# SunbotSchematic_copy.net
KiCad netlist of a schematic drawn in EAGLE
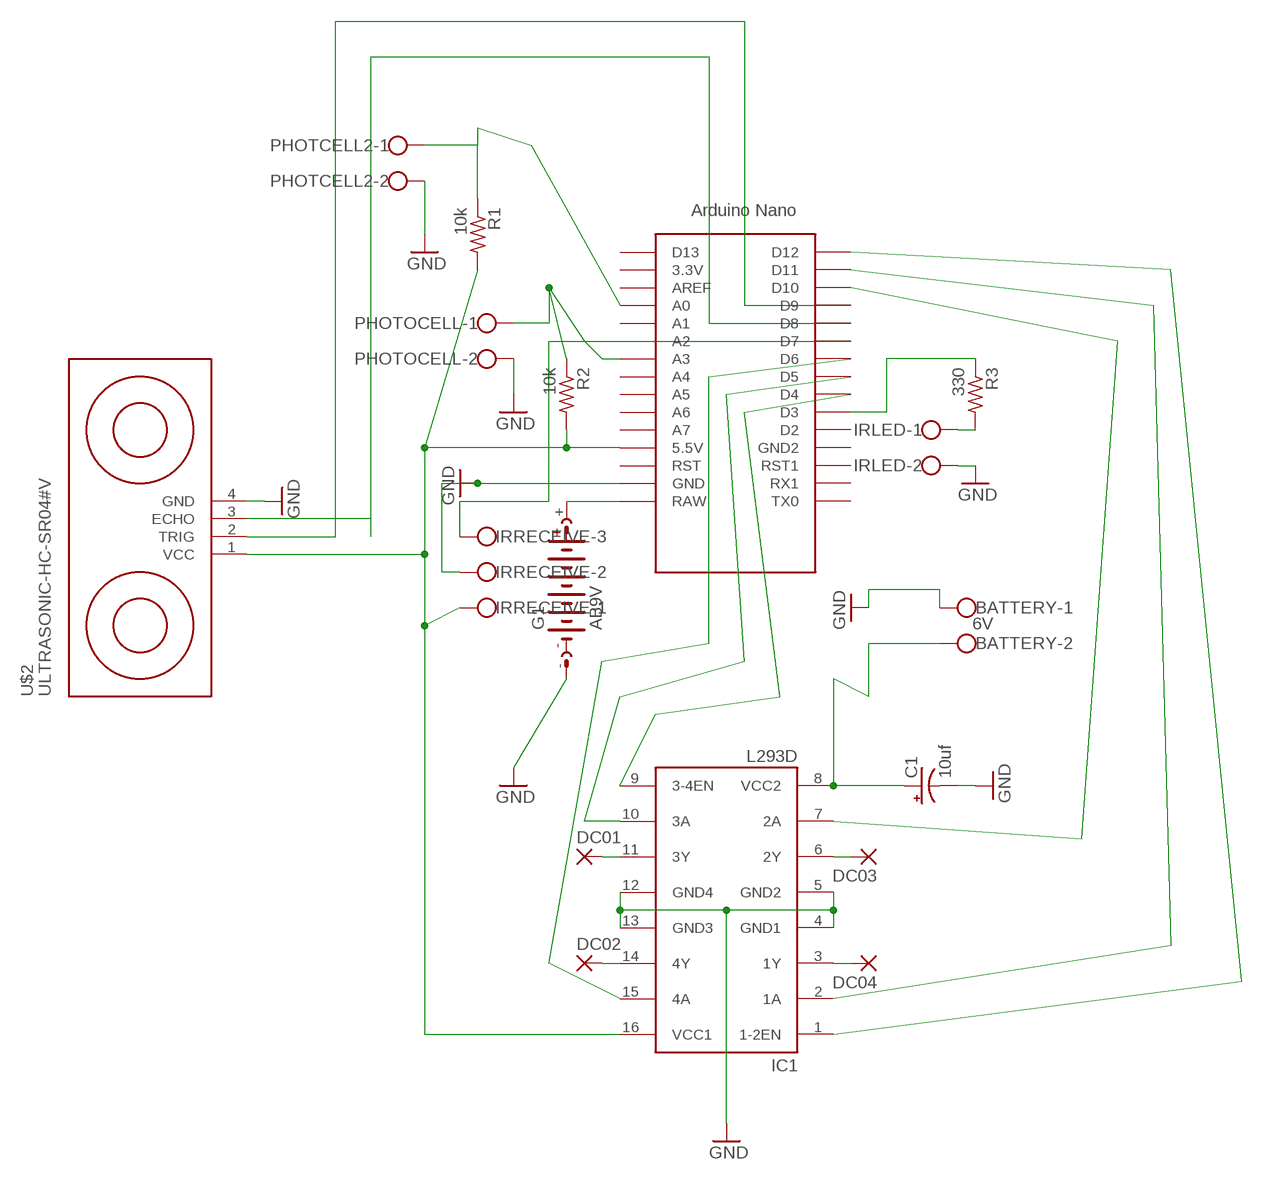
[diagram p0: schematic, sheet 1]

(export (version "E")
  (design (tool "Eeschema 10.0.6"))
  (components
    (comp (ref "BATTERY")
      (value "6V")
      (footprint "eagle-import:W237-102")
      (fields (field (name "MPN") "237-102"))
      (libsource (lib "eagle-import") (part "W237-102"))
    )
    (comp (ref "C1")
      (value "10uf")
      (footprint "eagle-import:E2-5")
      (libsource (lib "eagle-import") (part "CPOL-USE2-5"))
    )
    (comp (ref "DC01")
      (value "WIREPAD1,6/0,8")
      (footprint "eagle-import:1,6_0,8")
      (libsource (lib "eagle-import") (part "WIREPAD1,6/0,8"))
    )
    (comp (ref "DC02")
      (value "WIREPAD1,6/0,8")
      (footprint "eagle-import:1,6_0,8")
      (libsource (lib "eagle-import") (part "WIREPAD1,6/0,8"))
    )
    (comp (ref "DC03")
      (value "WIREPAD1,6/0,8")
      (footprint "eagle-import:1,6_0,8")
      (libsource (lib "eagle-import") (part "WIREPAD1,6/0,8"))
    )
    (comp (ref "DC04")
      (value "WIREPAD1,6/0,8")
      (footprint "eagle-import:1,6_0,8")
      (libsource (lib "eagle-import") (part "WIREPAD1,6/0,8"))
    )
    (comp (ref "G1")
      (value "AB9V")
      (footprint "eagle-import:AB9V")
      (libsource (lib "eagle-import") (part "AB9V"))
    )
    (comp (ref "IC1")
      (value "L293D")
      (footprint "eagle-import:DIL16")
      (libsource (lib "eagle-import") (part "L293D"))
    )
    (comp (ref "IRLED")
      (value "W237-102")
      (footprint "eagle-import:W237-102")
      (fields (field (name "MPN") "237-102"))
      (libsource (lib "eagle-import") (part "W237-102"))
    )
    (comp (ref "IRRECEIVE")
      (value "W237-103")
      (footprint "eagle-import:W237-103")
      (fields (field (name "MPN") "237-103"))
      (libsource (lib "eagle-import") (part "W237-103"))
    )
    (comp (ref "PHOTCELL2")
      (value "W237-102")
      (footprint "eagle-import:W237-102")
      (fields (field (name "MPN") "237-102"))
      (libsource (lib "eagle-import") (part "W237-102"))
    )
    (comp (ref "PHOTOCELL")
      (value "W237-102")
      (footprint "eagle-import:W237-102")
      (fields (field (name "MPN") "237-102"))
      (libsource (lib "eagle-import") (part "W237-102"))
    )
    (comp (ref "R1")
      (value "10k")
      (footprint "eagle-import:0204_7")
      (libsource (lib "eagle-import") (part "R-US_0204/7"))
    )
    (comp (ref "R2")
      (value "10k")
      (footprint "eagle-import:0204_7")
      (libsource (lib "eagle-import") (part "R-US_0204/7"))
    )
    (comp (ref "R3")
      (value "330")
      (footprint "eagle-import:0204_7")
      (libsource (lib "eagle-import") (part "R-US_0204/7"))
    )
    (comp (ref "U$1")
      (value "NANO")
      (footprint "eagle-import:NANO")
      (libsource (lib "eagle-import") (part "NANO"))
    )
    (comp (ref "U$2")
      (value "ULTRASONIC-HC-SR04#V")
      (footprint "eagle-import:ULTRASONIC-HC-SR04#V")
      (libsource (lib "eagle-import") (part "ULTRASONIC-HC-SR04#V"))
    )
  )
  (nets
    (net (code "1") (name "GND") (class "Default")
      (node (ref "BATTERY") (pin "1") (pinfunction "KL_1") (pintype "passive"))
      (node (ref "C1") (pin "-") (pinfunction "-_-") (pintype "passive"))
      (node (ref "G1") (pin "-") (pinfunction "-_-") (pintype "passive"))
      (node (ref "IC1") (pin "12") (pinfunction "GND4_12") (pintype "power_in"))
      (node (ref "IC1") (pin "13") (pinfunction "GND3_13") (pintype "power_in"))
      (node (ref "IC1") (pin "4") (pinfunction "GND1_4") (pintype "power_in"))
      (node (ref "IC1") (pin "5") (pinfunction "GND2_5") (pintype "power_in"))
      (node (ref "IRLED") (pin "2") (pinfunction "KL_2") (pintype "passive"))
      (node (ref "IRRECEIVE") (pin "2") (pinfunction "KL_2") (pintype "passive"))
      (node (ref "PHOTCELL2") (pin "2") (pinfunction "KL_2") (pintype "passive"))
      (node (ref "PHOTOCELL") (pin "2") (pinfunction "KL_2") (pintype "passive"))
      (node (ref "U$1") (pin "GND") (pinfunction "GND_GND") (pintype "bidirectional"))
      (node (ref "U$2") (pin "4") (pinfunction "GND_4") (pintype "power_in"))
    )
    (net (code "2") (name "Net-(BATTERYB-KL)") (class "Default")
      (node (ref "BATTERY") (pin "2") (pinfunction "KL_2") (pintype "passive"))
      (node (ref "C1") (pin "+") (pinfunction "+_+") (pintype "passive"))
      (node (ref "IC1") (pin "8") (pinfunction "VCC2_8") (pintype "power_in"))
    )
    (net (code "3") (name "Net-(DC01-P)") (class "Default")
      (node (ref "DC01") (pin "1") (pinfunction "P_1") (pintype "passive"))
      (node (ref "IC1") (pin "11") (pinfunction "3Y_11") (pintype "output"))
    )
    (net (code "4") (name "Net-(DC02-P)") (class "Default")
      (node (ref "DC02") (pin "1") (pinfunction "P_1") (pintype "passive"))
      (node (ref "IC1") (pin "14") (pinfunction "4Y_14") (pintype "output"))
    )
    (net (code "5") (name "Net-(DC03-P)") (class "Default")
      (node (ref "DC03") (pin "1") (pinfunction "P_1") (pintype "passive"))
      (node (ref "IC1") (pin "6") (pinfunction "2Y_6") (pintype "output"))
    )
    (net (code "6") (name "Net-(DC04-P)") (class "Default")
      (node (ref "DC04") (pin "1") (pinfunction "P_1") (pintype "passive"))
      (node (ref "IC1") (pin "3") (pinfunction "1Y_3") (pintype "output"))
    )
    (net (code "7") (name "Net-(G1-Pad+)") (class "Default")
      (node (ref "G1") (pin "+") (pinfunction "+_+") (pintype "passive"))
      (node (ref "U$1") (pin "RAW") (pinfunction "RAW_RAW") (pintype "bidirectional"))
    )
    (net (code "8") (name "Net-(IC1-1-2EN)") (class "Default")
      (node (ref "IC1") (pin "1") (pinfunction "1-2EN_1") (pintype "input"))
      (node (ref "U$1") (pin "D12") (pinfunction "D12_D12") (pintype "bidirectional"))
    )
    (net (code "9") (name "Net-(IC1-1A)") (class "Default")
      (node (ref "IC1") (pin "2") (pinfunction "1A_2") (pintype "input"))
      (node (ref "U$1") (pin "D11") (pinfunction "D11_D11") (pintype "bidirectional"))
    )
    (net (code "10") (name "Net-(IC1-2A)") (class "Default")
      (node (ref "IC1") (pin "7") (pinfunction "2A_7") (pintype "input"))
      (node (ref "U$1") (pin "D10") (pinfunction "D10_D10") (pintype "bidirectional"))
    )
    (net (code "11") (name "Net-(IC1-3-4EN)") (class "Default")
      (node (ref "IC1") (pin "9") (pinfunction "3-4EN_9") (pintype "input"))
      (node (ref "U$1") (pin "D4") (pinfunction "D4_D4") (pintype "bidirectional"))
    )
    (net (code "12") (name "Net-(IC1-3A)") (class "Default")
      (node (ref "IC1") (pin "10") (pinfunction "3A_10") (pintype "input"))
      (node (ref "U$1") (pin "D5") (pinfunction "D5_D5") (pintype "bidirectional"))
    )
    (net (code "13") (name "Net-(IC1-4A)") (class "Default")
      (node (ref "IC1") (pin "15") (pinfunction "4A_15") (pintype "input"))
      (node (ref "U$1") (pin "D6") (pinfunction "D6_D6") (pintype "bidirectional"))
    )
    (net (code "14") (name "Net-(IC1-VCC1)") (class "Default")
      (node (ref "IC1") (pin "16") (pinfunction "VCC1_16") (pintype "power_in"))
      (node (ref "IRRECEIVE") (pin "1") (pinfunction "KL_1") (pintype "passive"))
      (node (ref "R1") (pin "2") (pinfunction "2_2") (pintype "passive"))
      (node (ref "R2") (pin "2") (pinfunction "2_2") (pintype "passive"))
      (node (ref "U$1") (pin "5V") (pinfunction "5.5V_5V") (pintype "bidirectional"))
      (node (ref "U$2") (pin "1") (pinfunction "VCC_1") (pintype "power_in"))
    )
    (net (code "15") (name "Net-(IRLEDA-KL)") (class "Default")
      (node (ref "IRLED") (pin "1") (pinfunction "KL_1") (pintype "passive"))
      (node (ref "R3") (pin "2") (pinfunction "2_2") (pintype "passive"))
    )
    (net (code "16") (name "Net-(IRRECEIVEC-KL)") (class "Default")
      (node (ref "IRRECEIVE") (pin "3") (pinfunction "KL_3") (pintype "passive"))
      (node (ref "U$1") (pin "D7") (pinfunction "D7_D7") (pintype "bidirectional"))
    )
    (net (code "17") (name "Net-(PHOTCELL2A-KL)") (class "Default")
      (node (ref "PHOTCELL2") (pin "1") (pinfunction "KL_1") (pintype "passive"))
      (node (ref "R1") (pin "1") (pinfunction "1_1") (pintype "passive"))
      (node (ref "U$1") (pin "A0") (pinfunction "A0_A0") (pintype "bidirectional"))
    )
    (net (code "18") (name "Net-(PHOTOCELLA-KL)") (class "Default")
      (node (ref "PHOTOCELL") (pin "1") (pinfunction "KL_1") (pintype "passive"))
      (node (ref "R2") (pin "1") (pinfunction "1_1") (pintype "passive"))
      (node (ref "U$1") (pin "A3") (pinfunction "A3_A3") (pintype "bidirectional"))
    )
    (net (code "19") (name "Net-(R3-Pad1)") (class "Default")
      (node (ref "R3") (pin "1") (pinfunction "1_1") (pintype "passive"))
      (node (ref "U$1") (pin "D3") (pinfunction "D3_D3") (pintype "bidirectional"))
    )
    (net (code "20") (name "Net-(U$2-ECHO)") (class "Default")
      (node (ref "U$1") (pin "D8") (pinfunction "D8_D8") (pintype "bidirectional"))
      (node (ref "U$2") (pin "3") (pinfunction "ECHO_3") (pintype "output"))
    )
    (net (code "21") (name "Net-(U$2-TRIG)") (class "Default")
      (node (ref "U$1") (pin "D9") (pinfunction "D9_D9") (pintype "bidirectional"))
      (node (ref "U$2") (pin "2") (pinfunction "TRIG_2") (pintype "input"))
    )
    (net (code "22") (name "unconnected-(U$1-GND2-PadGND1)") (class "Default")
      (node (ref "U$1") (pin "GND1") (pinfunction "GND2_GND1") (pintype "bidirectional"))
    )
    (net (code "23") (name "unconnected-(U$1-Pad3.3V)") (class "Default")
      (node (ref "U$1") (pin "3.3V") (pinfunction "3.3V_3.3V") (pintype "bidirectional"))
    )
    (net (code "24") (name "unconnected-(U$1-PadA1)") (class "Default")
      (node (ref "U$1") (pin "A1") (pinfunction "A1_A1") (pintype "bidirectional"))
    )
    (net (code "25") (name "unconnected-(U$1-PadA2)") (class "Default")
      (node (ref "U$1") (pin "A2") (pinfunction "A2_A2") (pintype "bidirectional"))
    )
    (net (code "26") (name "unconnected-(U$1-PadA4)") (class "Default")
      (node (ref "U$1") (pin "A4") (pinfunction "A4_A4") (pintype "bidirectional"))
    )
    (net (code "27") (name "unconnected-(U$1-PadA5)") (class "Default")
      (node (ref "U$1") (pin "A5") (pinfunction "A5_A5") (pintype "bidirectional"))
    )
    (net (code "28") (name "unconnected-(U$1-PadA6)") (class "Default")
      (node (ref "U$1") (pin "A6") (pinfunction "A6_A6") (pintype "bidirectional"))
    )
    (net (code "29") (name "unconnected-(U$1-PadA7)") (class "Default")
      (node (ref "U$1") (pin "A7") (pinfunction "A7_A7") (pintype "bidirectional"))
    )
    (net (code "30") (name "unconnected-(U$1-PadAREF)") (class "Default")
      (node (ref "U$1") (pin "AREF") (pinfunction "AREF_AREF") (pintype "bidirectional"))
    )
    (net (code "31") (name "unconnected-(U$1-PadD2)") (class "Default")
      (node (ref "U$1") (pin "D2") (pinfunction "D2_D2") (pintype "bidirectional"))
    )
    (net (code "32") (name "unconnected-(U$1-PadD13)") (class "Default")
      (node (ref "U$1") (pin "D13") (pinfunction "D13_D13") (pintype "bidirectional"))
    )
    (net (code "33") (name "unconnected-(U$1-PadICSP1)") (class "Default")
      (node (ref "U$1") (pin "ICSP1") (pinfunction "ICSP1_ICSP1") (pintype "bidirectional"))
    )
    (net (code "34") (name "unconnected-(U$1-PadICSP2)") (class "Default")
      (node (ref "U$1") (pin "ICSP2") (pinfunction "ICSP2_ICSP2") (pintype "bidirectional"))
    )
    (net (code "35") (name "unconnected-(U$1-PadICSP3)") (class "Default")
      (node (ref "U$1") (pin "ICSP3") (pinfunction "ICSP3_ICSP3") (pintype "bidirectional"))
    )
    (net (code "36") (name "unconnected-(U$1-PadICSP4)") (class "Default")
      (node (ref "U$1") (pin "ICSP4") (pinfunction "ICSP4_ICSP4") (pintype "bidirectional"))
    )
    (net (code "37") (name "unconnected-(U$1-PadICSP5)") (class "Default")
      (node (ref "U$1") (pin "ICSP5") (pinfunction "ICSP5_ICSP5") (pintype "bidirectional"))
    )
    (net (code "38") (name "unconnected-(U$1-PadICSP6)") (class "Default")
      (node (ref "U$1") (pin "ICSP6") (pinfunction "ICSP6_ICSP6") (pintype "bidirectional"))
    )
    (net (code "39") (name "unconnected-(U$1-PadRST)") (class "Default")
      (node (ref "U$1") (pin "RST") (pinfunction "RST_RST") (pintype "bidirectional"))
    )
    (net (code "40") (name "unconnected-(U$1-PadRST1)") (class "Default")
      (node (ref "U$1") (pin "RST1") (pinfunction "RST1_RST1") (pintype "bidirectional"))
    )
    (net (code "41") (name "unconnected-(U$1-PadRX1)") (class "Default")
      (node (ref "U$1") (pin "RX1") (pinfunction "RX1_RX1") (pintype "bidirectional"))
    )
    (net (code "42") (name "unconnected-(U$1-PadTX0)") (class "Default")
      (node (ref "U$1") (pin "TX0") (pinfunction "TX0_TX0") (pintype "bidirectional"))
    )
  )
)
